# Input.net
KiCad netlist of a schematic drawn in Altium Designer
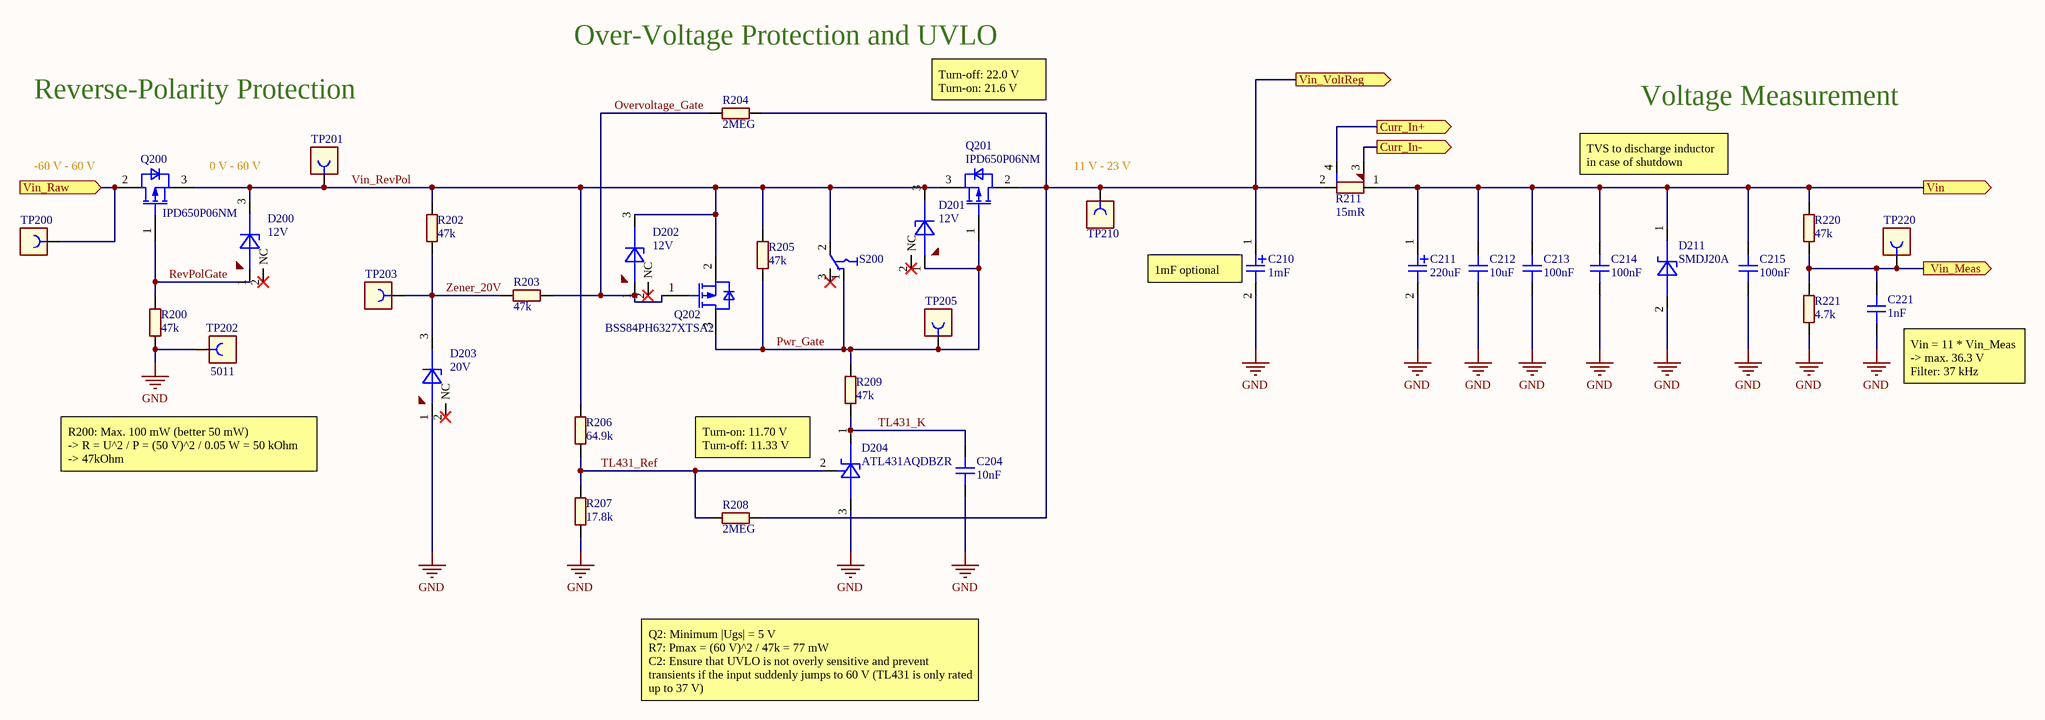
[diagram p0: Input.SchDoc]

(export (version "E")
  (design (tool "Eeschema 10.0.6"))
  (components
    (comp (ref "C204")
      (value "10nF")
      (footprint "CAPC1608X90N-4")
      (description "CAP / CERA / 10nF / 50V / 10% / X8R (EIA) / -55°C to 150°C / 0603(1608) / SMD / -")
      (fields
        (field (name "LEGACY PARTNUMBER") "CAP01010834")
        (field (name "MANUFACTURER") "TDK Corporation")
      )
      (libsource (lib "PCBLibraryData") (part "CAP-SGL-STD-02P_00000001"))
    )
    (comp (ref "C210")
      (value "1mF")
      (footprint "CAPPRD500W60D1300H2700B")
      (fields (field (name "MANUFACTURER") "Kemet"))
      (libsource (lib "PCBLibraryData") (part "CAP-SGL-POL-02P_00000002"))
    )
    (comp (ref "C211")
      (value "220uF")
      (footprint "CAPAE1030X1050N-2")
      (fields (field (name "MANUFACTURER") "Wurth Elektronik"))
      (libsource (lib "PCBLibraryData") (part "CAP-SGL-POL-02P_00000002"))
    )
    (comp (ref "C212")
      (value "10uF")
      (footprint "CAPC3216X190N-1")
      (description "CAP / CERA / 10uF / 50V / 20% / X5R (EIA) / -55°C to 85°C / 1206 (3216) / SMD / -")
      (fields (field (name "MANUFACTURER") "Taiyo Yuden"))
      (libsource (lib "PCBLibraryData") (part "CAP-SGL-STD-02P_00000001"))
    )
    (comp (ref "C213")
      (value "100nF")
      (footprint "CAPC1608X90N-2")
      (description "CAP / CERA / 100nF / 50V / 10% / X7R (EIA) / -55°C to 125°C / 0603 / SMD / -")
      (fields (field (name "MANUFACTURER") "AVX"))
      (libsource (lib "PCBLibraryData") (part "CAP-SGL-STD-02P_00000001"))
    )
    (comp (ref "C214")
      (value "100nF")
      (footprint "CAPC1608X90N-2")
      (description "CAP / CERA / 100nF / 50V / 10% / X7R (EIA) / -55°C to 125°C / 0603 / SMD / -")
      (fields (field (name "MANUFACTURER") "AVX"))
      (libsource (lib "PCBLibraryData") (part "CAP-SGL-STD-02P_00000001"))
    )
    (comp (ref "C215")
      (value "100nF")
      (footprint "CAPC1608X90N-2")
      (description "CAP / CERA / 100nF / 50V / 10% / X7R (EIA) / -55°C to 125°C / 0603 / SMD / -")
      (fields (field (name "MANUFACTURER") "AVX"))
      (libsource (lib "PCBLibraryData") (part "CAP-SGL-STD-02P_00000001"))
    )
    (comp (ref "C221")
      (value "1nF")
      (footprint "CAPC1608X87N-1")
      (description "CAP / CERA / 1nF / 50V / 10% / X7R (EIA) / -55°C to 125°C / 0603 (1608) / SMD / -")
      (fields (field (name "MANUFACTURER") "Wurth Elektronik"))
      (libsource (lib "PCBLibraryData") (part "CAP-SGL-STD-02P_00000001"))
    )
    (comp (ref "D200")
      (value "12V")
      (footprint "SOT95P237X111-3N-1")
      (description "Zener Voltage Regulator, 250 mW, 12V")
      (fields (field (name "MANUFACTURER") "ON Semiconductor"))
      (libsource (lib "PCBLibraryData") (part "d_zener_a1c3_3p"))
    )
    (comp (ref "D201")
      (value "12V")
      (footprint "SOT95P237X111-3N-1")
      (description "Zener Voltage Regulator, 250 mW, 12V")
      (fields (field (name "MANUFACTURER") "ON Semiconductor"))
      (libsource (lib "PCBLibraryData") (part "d_zener_a1c3_3p"))
    )
    (comp (ref "D202")
      (value "12V")
      (footprint "SOT95P237X111-3N-1")
      (description "Zener Voltage Regulator, 250 mW, 12V")
      (fields (field (name "MANUFACTURER") "ON Semiconductor"))
      (libsource (lib "PCBLibraryData") (part "d_zener_a1c3_3p"))
    )
    (comp (ref "D203")
      (value "20V")
      (footprint "SOT95P237X111-3N-1")
      (description "Zener Voltage Regulators")
      (fields (field (name "MANUFACTURER") "ON Semiconductor"))
      (libsource (lib "PCBLibraryData") (part "d_zener_a1c3_3p"))
    )
    (comp (ref "D204")
      (value "ATL431AQDBZR")
      (footprint "SOT95P237X112-3N-1")
      (description "ATL431 Adjustable Precision Shunt Regulator")
      (fields (field (name "MANUFACTURER") "Texas Instruments"))
      (libsource (lib "PCBLibraryData") (part "d_tvs_c1a3_3p"))
    )
    (comp (ref "D211")
      (value "SMDJ20A")
      (footprint "DIOM7959X262N")
      (description "TVS Diode, Low Profile Package, Built in Strain Relief, Glass Passivated Chip Junction")
      (fields (field (name "MANUFACTURER") "Littelfuse"))
      (libsource (lib "PCBLibraryData") (part "d_tvs_a"))
    )
    (comp (ref "Q200")
      (value "IPD650P06NM")
      (footprint "TO228P998X250-3N-V2")
      (description "OptiMOS Power Transistor, -60 V")
      (fields (field (name "MANUFACTURER") "Infineon Technologies"))
      (libsource (lib "PCBLibraryData") (part "igfet_p_ch_enh_dio_1g2d3s_3p"))
    )
    (comp (ref "Q201")
      (value "IPD650P06NM")
      (footprint "TO228P998X250-3N-V2")
      (description "OptiMOS Power Transistor, -60 V")
      (fields (field (name "MANUFACTURER") "Infineon Technologies"))
      (libsource (lib "PCBLibraryData") (part "igfet_p_ch_enh_dio_1g2d3s_3p"))
    )
    (comp (ref "Q202")
      (value "BSS84PH6327XTSA2")
      (footprint "SOT95P240X110-3N-1")
      (description "SIPMOS P-Channel Enhancement Small-Signal-Transistor")
      (fields
        (field (name "LEGACY PARTNUMBER") "IFX01400461")
        (field (name "MANUFACTURER") "Infineon Technologies")
      )
      (libsource (lib "PCBLibraryData") (part "igfet_p_ch_enh_dio_1g2s3d_3p"))
    )
    (comp (ref "R200")
      (value "47k")
      (footprint "RESC1609X50N")
      (description "RES / STD / 47k / 100mW / 1% / 100ppm/K / -55°C to 155°C / 0603 / SMD / -")
      (fields (field (name "LEGACY PARTNUMBER") "RES01801333") (field (name "MANUFACTURER") "Vishay"))
      (libsource (lib "PCBLibraryData") (part "RES-SGL-STD-02P_00000006"))
    )
    (comp (ref "R202")
      (value "47k")
      (footprint "RESC1609X50N")
      (description "RES / STD / 47k / 100mW / 1% / 100ppm/K / -55°C to 155°C / 0603 / SMD / -")
      (fields (field (name "LEGACY PARTNUMBER") "RES01801333") (field (name "MANUFACTURER") "Vishay"))
      (libsource (lib "PCBLibraryData") (part "RES-SGL-STD-02P_00000006"))
    )
    (comp (ref "R203")
      (value "47k")
      (footprint "RESC1609X50N")
      (description "RES / STD / 47k / 100mW / 1% / 100ppm/K / -55°C to 155°C / 0603 / SMD / -")
      (fields (field (name "LEGACY PARTNUMBER") "RES01801333") (field (name "MANUFACTURER") "Vishay"))
      (libsource (lib "") (part "RES-SGL-STD-02P_00000006_1"))
    )
    (comp (ref "R204")
      (value "2MEG")
      (footprint "RESC1609X50N")
      (description "RES / STD / 2MEG / 100mW / 1% / 100ppm/K / -55°C to 155°C / 0603 / SMD / -")
      (fields (field (name "LEGACY PARTNUMBER") "RES01801517") (field (name "MANUFACTURER") "Vishay"))
      (libsource (lib "") (part "RES-SGL-STD-02P_00000006_2"))
    )
    (comp (ref "R205")
      (value "47k")
      (footprint "RESC1609X50N")
      (description "RES / STD / 47k / 100mW / 1% / 100ppm/K / -55°C to 155°C / 0603 / SMD / -")
      (fields (field (name "LEGACY PARTNUMBER") "RES01801333") (field (name "MANUFACTURER") "Vishay"))
      (libsource (lib "PCBLibraryData") (part "RES-SGL-STD-02P_00000006"))
    )
    (comp (ref "R206")
      (value "64.9k")
      (footprint "RESC1609X50N")
      (description "RES / STD / 64.9k / 100mW / 1% / 100ppm/K / -55°C to 155°C / 0603 / SMD / -")
      (fields (field (name "LEGACY PARTNUMBER") "RES01801350") (field (name "MANUFACTURER") "Vishay"))
      (libsource (lib "PCBLibraryData") (part "RES-SGL-STD-02P_00000006"))
    )
    (comp (ref "R207")
      (value "17.8k")
      (footprint "RESC1609X50N")
      (description "RES / STD / 17.8k / 100mW / 1% / 100ppm/K / -55°C to 155°C / 0603 / SMD / -")
      (fields (field (name "LEGACY PARTNUMBER") "RES01801283") (field (name "MANUFACTURER") "Vishay"))
      (libsource (lib "PCBLibraryData") (part "RES-SGL-STD-02P_00000006"))
    )
    (comp (ref "R208")
      (value "2MEG")
      (footprint "RESC1609X50N")
      (description "RES / STD / 2MEG / 100mW / 1% / 100ppm/K / -55°C to 155°C / 0603 / SMD / -")
      (fields (field (name "LEGACY PARTNUMBER") "RES01801517") (field (name "MANUFACTURER") "Vishay"))
      (libsource (lib "") (part "RES-SGL-STD-02P_00000006_2"))
    )
    (comp (ref "R209")
      (value "47k")
      (footprint "RESC1609X50N")
      (description "RES / STD / 47k / 100mW / 1% / 100ppm/K / -55°C to 155°C / 0603 / SMD / -")
      (fields (field (name "LEGACY PARTNUMBER") "RES01801333") (field (name "MANUFACTURER") "Vishay"))
      (libsource (lib "PCBLibraryData") (part "RES-SGL-STD-02P_00000006"))
    )
    (comp (ref "R211")
      (value "15mR")
      (footprint "RES-SMD-L4T12")
      (description "RES / STD / 15mR / 500mW / 1% / 75ppm/K / -55°C to 155°C / 1206 (3216) / SMD / -")
      (fields (field (name "MANUFACTURER") "Ohmite"))
      (libsource (lib "PCBLibraryData") (part "RES-SHT-STD-04P_00097BE5"))
    )
    (comp (ref "R220")
      (value "47k")
      (footprint "RESC1609X50N")
      (description "RES / STD / 47k / 100mW / 1% / 100ppm/K / -55°C to 155°C / 0603 / SMD / -")
      (fields (field (name "LEGACY PARTNUMBER") "RES01801333") (field (name "MANUFACTURER") "Vishay"))
      (libsource (lib "") (part "RES-SGL-STD-02P_00000006_3"))
    )
    (comp (ref "R221")
      (value "4.7k")
      (footprint "RESC1609X50N")
      (description "RES / STD / 4.7k / 100mW / 1% / 100ppm/K / -55°C to 155°C / 0603 / SMD / -")
      (fields (field (name "LEGACY PARTNUMBER") "RES01801219") (field (name "MANUFACTURER") "Vishay"))
      (libsource (lib "PCBLibraryData") (part "RES-SGL-STD-02P_00000006"))
    )
    (comp (ref "S200")
      (value "CL-SB-12A-01T")
      (footprint "SW-SMD-CL-SB-12A-01T")
      (description "Slid Switch, 12V, 200mA")
      (fields (field (name "MANUFACTURER") "NIDEC COPAL ELECTRONICS, Inc."))
      (libsource (lib "PCBLibraryData") (part "sw_co213_3p"))
    )
    (comp (ref "TP200")
      (value "S1751-46R")
      (footprint "CON-SMD-TT-S1751-46")
      (description "Test Terminal, Surface Mount (Tape and Reeled Components)")
      (fields (field (name "LEGACY PARTNUMBER") "CON01501015") (field (name "MANUFACTURER") "Harwin"))
      (libsource (lib "PCBLibraryData") (part "connector_1_f"))
    )
    (comp (ref "TP201")
      (value "S1751-46R")
      (footprint "CON-SMD-TT-S1751-46")
      (description "Test Terminal, Surface Mount (Tape and Reeled Components)")
      (fields (field (name "LEGACY PARTNUMBER") "CON01501015") (field (name "MANUFACTURER") "Harwin"))
      (libsource (lib "") (part "connector_1_f_3"))
    )
    (comp (ref "TP202")
      (value "5011")
      (footprint "CON-THT-TP-5011")
      (description "PC Test Point-Multipurpose THT, Black")
      (fields
        (field (name "LEGACY PARTNUMBER") "CON01500530")
        (field (name "MANUFACTURER") "Keystone Electronics Corp.")
      )
      (libsource (lib "") (part "connector_1_f_1"))
    )
    (comp (ref "TP203")
      (value "S1751-46R")
      (footprint "CON-SMD-TT-S1751-46")
      (description "Test Terminal, Surface Mount (Tape and Reeled Components)")
      (fields (field (name "LEGACY PARTNUMBER") "CON01501015") (field (name "MANUFACTURER") "Harwin"))
      (libsource (lib "PCBLibraryData") (part "connector_1_f"))
    )
    (comp (ref "TP205")
      (value "S1751-46R")
      (footprint "CON-SMD-TT-S1751-46")
      (description "Test Terminal, Surface Mount (Tape and Reeled Components)")
      (fields (field (name "LEGACY PARTNUMBER") "CON01501015") (field (name "MANUFACTURER") "Harwin"))
      (libsource (lib "") (part "connector_1_f_3"))
    )
    (comp (ref "TP210")
      (value "S1751-46R")
      (footprint "CON-SMD-TT-S1751-46")
      (description "Test Terminal, Surface Mount (Tape and Reeled Components)")
      (fields (field (name "LEGACY PARTNUMBER") "CON01501015") (field (name "MANUFACTURER") "Harwin"))
      (libsource (lib "") (part "connector_1_f_2"))
    )
    (comp (ref "TP220")
      (value "S1751-46R")
      (footprint "CON-SMD-TT-S1751-46")
      (description "Test Terminal, Surface Mount (Tape and Reeled Components)")
      (fields (field (name "LEGACY PARTNUMBER") "CON01501015") (field (name "MANUFACTURER") "Harwin"))
      (libsource (lib "") (part "connector_1_f_3"))
    )
  )
  (nets
    (net (code "1") (name "/Curr_In+") (class "Default")
      (node (ref "R211") (pin "4") (pinfunction "I2_4") (pintype "passive"))
    )
    (net (code "2") (name "/Curr_In-") (class "Default")
      (node (ref "R211") (pin "3") (pinfunction "I1_3") (pintype "passive"))
    )
    (net (code "3") (name "/Overvoltage_Gate") (class "Default")
      (node (ref "D202") (pin "1") (pinfunction "ANODE_1") (pintype "passive"))
      (node (ref "Q202") (pin "1") (pinfunction "GATE_1") (pintype "passive"))
      (node (ref "R203") (pin "1") (pinfunction "1_1") (pintype "passive"))
      (node (ref "R204") (pin "1") (pinfunction "1_1") (pintype "passive"))
    )
    (net (code "4") (name "/Pwr_Gate") (class "Default")
      (node (ref "D201") (pin "1") (pinfunction "ANODE_1") (pintype "passive"))
      (node (ref "Q201") (pin "1") (pinfunction "GATE_1") (pintype "passive"))
      (node (ref "Q202") (pin "3") (pinfunction "DRAIN_3") (pintype "passive"))
      (node (ref "R205") (pin "1") (pinfunction "1_1") (pintype "passive"))
      (node (ref "R209") (pin "2") (pinfunction "2_2") (pintype "passive"))
      (node (ref "S200") (pin "1") (pinfunction "1_1") (pintype "passive"))
      (node (ref "TP205") (pin "1") (pinfunction "1_1") (pintype "passive"))
    )
    (net (code "5") (name "/RevPolGate") (class "Default")
      (node (ref "D200") (pin "1") (pinfunction "ANODE_1") (pintype "passive"))
      (node (ref "Q200") (pin "1") (pinfunction "GATE_1") (pintype "passive"))
      (node (ref "R200") (pin "2") (pinfunction "2_2") (pintype "passive"))
    )
    (net (code "6") (name "/TL431_K") (class "Default")
      (node (ref "C204") (pin "2") (pinfunction "2_2") (pintype "passive"))
      (node (ref "D204") (pin "1") (pinfunction "CATHODE_1") (pintype "passive"))
      (node (ref "R209") (pin "1") (pinfunction "1_1") (pintype "passive"))
    )
    (net (code "7") (name "/TL431_Ref") (class "Default")
      (node (ref "D204") (pin "2") (pinfunction "REF_2") (pintype "passive"))
      (node (ref "R206") (pin "1") (pinfunction "1_1") (pintype "passive"))
      (node (ref "R207") (pin "2") (pinfunction "2_2") (pintype "passive"))
      (node (ref "R208") (pin "1") (pinfunction "1_1") (pintype "passive"))
    )
    (net (code "8") (name "/Vin") (class "Default")
      (node (ref "C211") (pin "1") (pinfunction "1_1") (pintype "passive"))
      (node (ref "C212") (pin "2") (pinfunction "2_2") (pintype "passive"))
      (node (ref "C213") (pin "2") (pinfunction "2_2") (pintype "passive"))
      (node (ref "C214") (pin "2") (pinfunction "2_2") (pintype "passive"))
      (node (ref "C215") (pin "2") (pinfunction "2_2") (pintype "passive"))
      (node (ref "D211") (pin "1") (pinfunction "CATHODE_1") (pintype "passive"))
      (node (ref "R211") (pin "1") (pinfunction "V1_1") (pintype "passive"))
      (node (ref "R220") (pin "1") (pinfunction "1_1") (pintype "passive"))
    )
    (net (code "9") (name "/Vin_Meas") (class "Default")
      (node (ref "C221") (pin "2") (pinfunction "2_2") (pintype "passive"))
      (node (ref "R220") (pin "2") (pinfunction "2_2") (pintype "passive"))
      (node (ref "R221") (pin "2") (pinfunction "2_2") (pintype "passive"))
      (node (ref "TP220") (pin "1") (pinfunction "1_1") (pintype "passive"))
    )
    (net (code "10") (name "/Vin_Raw") (class "Default")
      (node (ref "Q200") (pin "2") (pinfunction "DRAIN_2") (pintype "passive"))
      (node (ref "TP200") (pin "1") (pinfunction "1_1") (pintype "passive"))
    )
    (net (code "11") (name "/Vin_RevPol") (class "Default")
      (node (ref "D200") (pin "3") (pinfunction "CATHODE_3") (pintype "passive"))
      (node (ref "D201") (pin "3") (pinfunction "CATHODE_3") (pintype "passive"))
      (node (ref "D202") (pin "3") (pinfunction "CATHODE_3") (pintype "passive"))
      (node (ref "Q200") (pin "3") (pinfunction "SOURCE_3") (pintype "passive"))
      (node (ref "Q201") (pin "3") (pinfunction "SOURCE_3") (pintype "passive"))
      (node (ref "Q202") (pin "2") (pinfunction "SOURCE_2") (pintype "passive"))
      (node (ref "R202") (pin "2") (pinfunction "2_2") (pintype "passive"))
      (node (ref "R205") (pin "2") (pinfunction "2_2") (pintype "passive"))
      (node (ref "R206") (pin "2") (pinfunction "2_2") (pintype "passive"))
      (node (ref "S200") (pin "2") (pinfunction "2_2") (pintype "passive"))
      (node (ref "TP201") (pin "1") (pinfunction "1_1") (pintype "passive"))
    )
    (net (code "12") (name "/Vin_VoltReg") (class "Default")
      (node (ref "C210") (pin "1") (pinfunction "1_1") (pintype "passive"))
      (node (ref "Q201") (pin "2") (pinfunction "DRAIN_2") (pintype "passive"))
      (node (ref "R204") (pin "2") (pinfunction "2_2") (pintype "passive"))
      (node (ref "R208") (pin "2") (pinfunction "2_2") (pintype "passive"))
      (node (ref "R211") (pin "2") (pinfunction "V2_2") (pintype "passive"))
      (node (ref "TP210") (pin "1") (pinfunction "1_1") (pintype "passive"))
    )
    (net (code "13") (name "/Zener_20V") (class "Default")
      (node (ref "D203") (pin "3") (pinfunction "CATHODE_3") (pintype "passive"))
      (node (ref "R202") (pin "1") (pinfunction "1_1") (pintype "passive"))
      (node (ref "R203") (pin "2") (pinfunction "2_2") (pintype "passive"))
      (node (ref "TP203") (pin "1") (pinfunction "1_1") (pintype "passive"))
    )
    (net (code "14") (name "GND") (class "Default")
      (node (ref "C204") (pin "1") (pinfunction "1_1") (pintype "passive"))
      (node (ref "C210") (pin "2") (pinfunction "2_2") (pintype "passive"))
      (node (ref "C211") (pin "2") (pinfunction "2_2") (pintype "passive"))
      (node (ref "C212") (pin "1") (pinfunction "1_1") (pintype "passive"))
      (node (ref "C213") (pin "1") (pinfunction "1_1") (pintype "passive"))
      (node (ref "C214") (pin "1") (pinfunction "1_1") (pintype "passive"))
      (node (ref "C215") (pin "1") (pinfunction "1_1") (pintype "passive"))
      (node (ref "C221") (pin "1") (pinfunction "1_1") (pintype "passive"))
      (node (ref "D203") (pin "1") (pinfunction "ANODE_1") (pintype "passive"))
      (node (ref "D204") (pin "3") (pinfunction "ANODE_3") (pintype "passive"))
      (node (ref "D211") (pin "2") (pinfunction "ANODE_2") (pintype "passive"))
      (node (ref "R200") (pin "1") (pinfunction "1_1") (pintype "passive"))
      (node (ref "R207") (pin "1") (pinfunction "1_1") (pintype "passive"))
      (node (ref "R221") (pin "1") (pinfunction "1_1") (pintype "passive"))
      (node (ref "TP202") (pin "1") (pinfunction "1_1") (pintype "passive"))
    )
    (net (code "15") (name "unconnected-(D200-NC-Pad2)") (class "Default")
      (node (ref "D200") (pin "2") (pinfunction "NC_2") (pintype "passive+no_connect"))
    )
    (net (code "16") (name "unconnected-(D201-NC-Pad2)") (class "Default")
      (node (ref "D201") (pin "2") (pinfunction "NC_2") (pintype "passive+no_connect"))
    )
    (net (code "17") (name "unconnected-(D202-NC-Pad2)") (class "Default")
      (node (ref "D202") (pin "2") (pinfunction "NC_2") (pintype "passive+no_connect"))
    )
    (net (code "18") (name "unconnected-(D203-NC-Pad2)") (class "Default")
      (node (ref "D203") (pin "2") (pinfunction "NC_2") (pintype "passive+no_connect"))
    )
    (net (code "19") (name "unconnected-(S200-Pad3)") (class "Default")
      (node (ref "S200") (pin "3") (pinfunction "3_3") (pintype "passive+no_connect"))
    )
  )
)
